# AK9750_Human_Movement_Sensor_Breakout.net
KiCad netlist of a schematic drawn in EAGLE
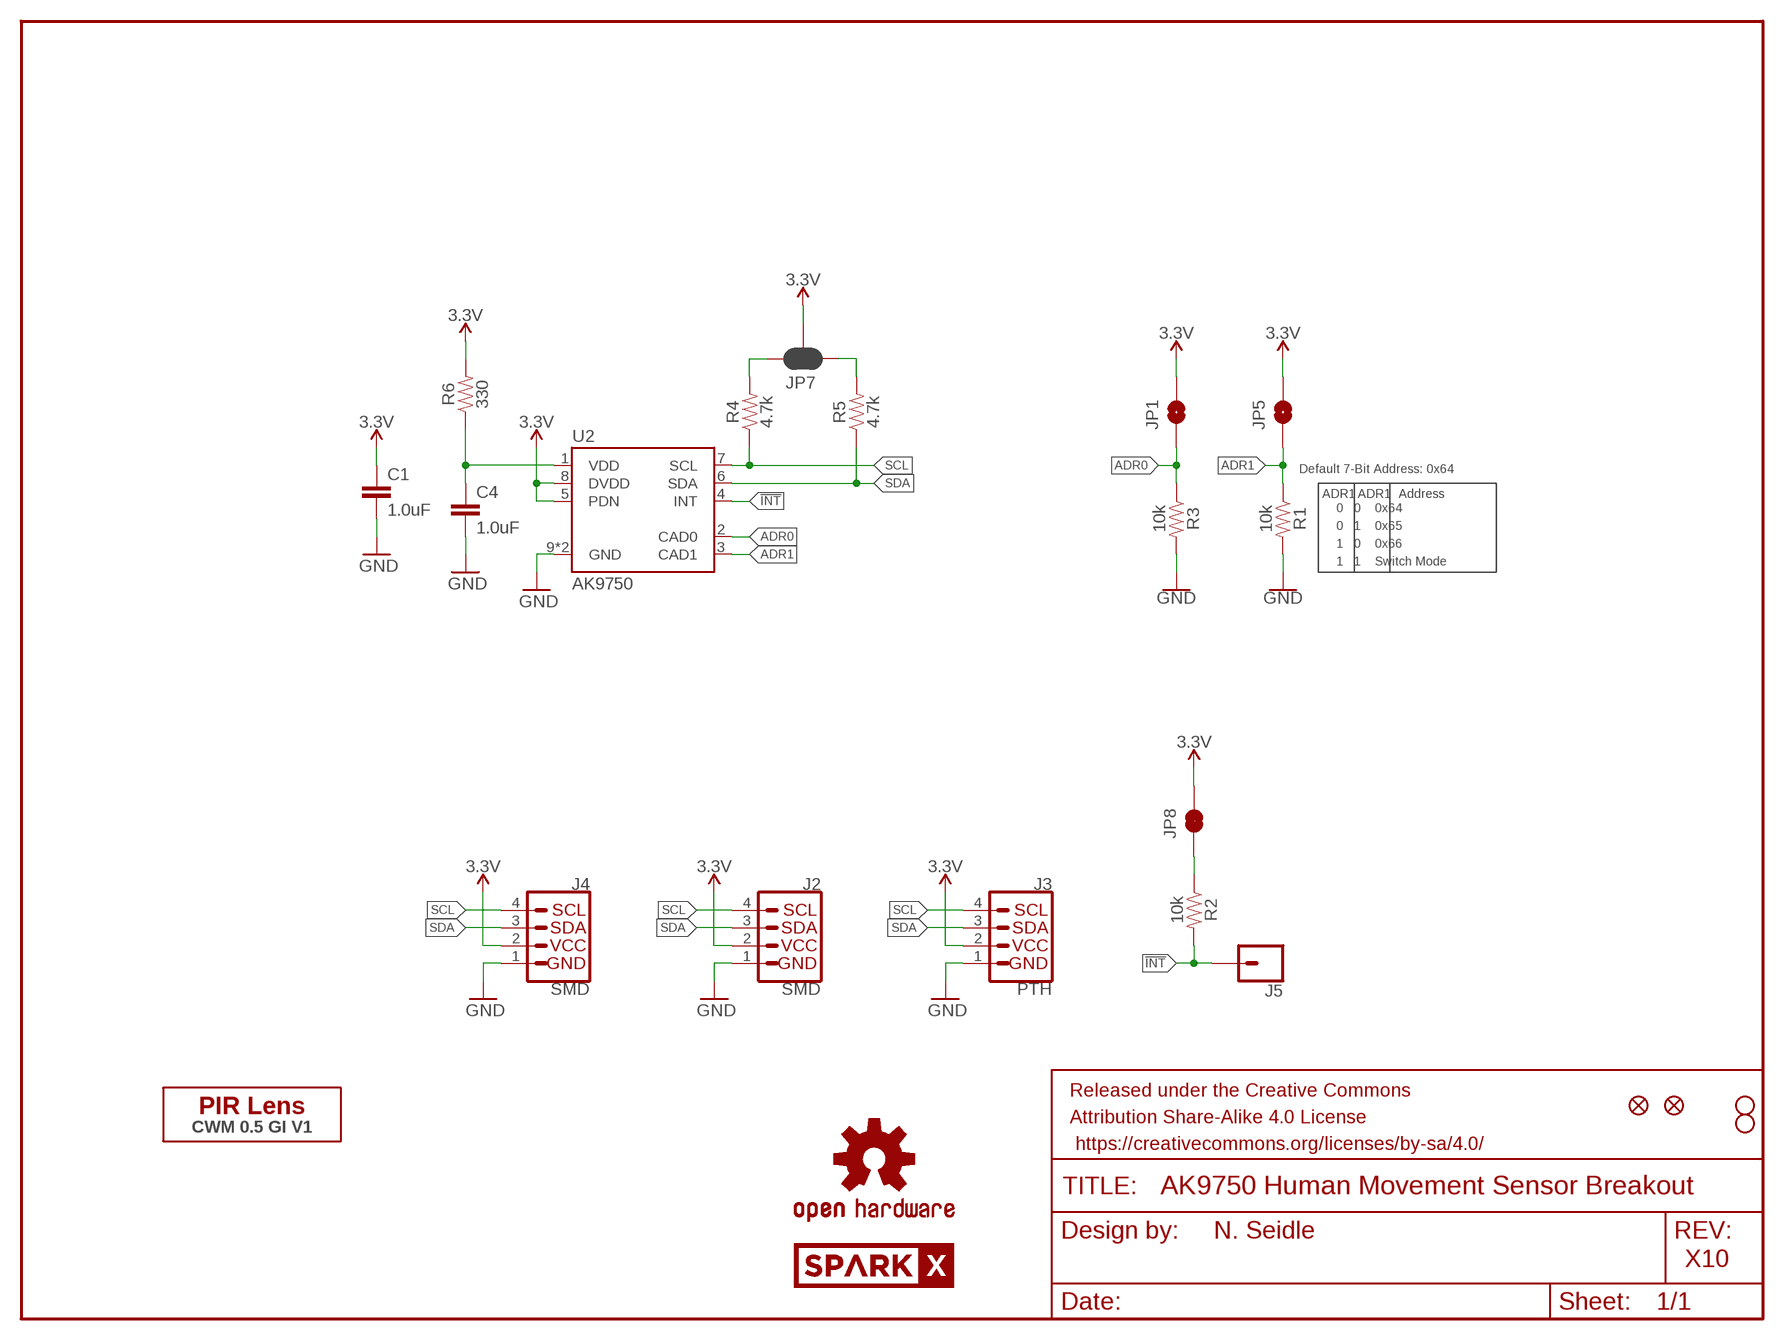
[diagram p0: schematic, sheet 1]

(export (version "E")
  (design (tool "Eeschema 10.0.6"))
  (components
    (comp (ref "C1")
      (value "1.0uF")
      (footprint "eagle-import:0603")
      (libsource (lib "eagle-import") (part "1.0UF-0603-16V-10%"))
    )
    (comp (ref "C4")
      (value "1.0uF")
      (footprint "eagle-import:0603")
      (libsource (lib "eagle-import") (part "1.0UF-0603-16V-10%"))
    )
    (comp (ref "FRAME1")
      (value "FRAME-LETTER")
      (footprint "eagle-import:CREATIVE_COMMONS")
      (libsource (lib "eagle-import") (part "FRAME-LETTER"))
    )
    (comp (ref "J2")
      (value "SMD")
      (footprint "eagle-import:1X04_1MM_RA")
      (libsource (lib "eagle-import") (part "I2C_STANDARDJS-1MM"))
    )
    (comp (ref "J3")
      (value "PTH")
      (footprint "eagle-import:1X04_NO_SILK")
      (libsource (lib "eagle-import") (part "I2C_STANDARD_NO_SILK"))
    )
    (comp (ref "J4")
      (value "SMD")
      (footprint "eagle-import:1X04_1MM_RA")
      (libsource (lib "eagle-import") (part "I2C_STANDARDJS-1MM"))
    )
    (comp (ref "J5")
      (value "CONN_01PTH_NO_SILK_YES_STOP")
      (footprint "eagle-import:1X01_NO_SILK")
      (libsource (lib "eagle-import") (part "CONN_01PTH_NO_SILK_YES_STOP"))
    )
    (comp (ref "JP1")
      (value "JUMPER-SMT_2_NO_SILK")
      (footprint "eagle-import:SMT-JUMPER_2_NO_SILK")
      (libsource (lib "eagle-import") (part "JUMPER-SMT_2_NO_SILK"))
    )
    (comp (ref "JP2")
      (value "FIDUCIALUFIDUCIAL")
      (footprint "eagle-import:MICRO-FIDUCIAL")
      (libsource (lib "eagle-import") (part "FIDUCIALUFIDUCIAL"))
    )
    (comp (ref "JP3")
      (value "STAND-OFF")
      (footprint "eagle-import:STAND-OFF")
      (libsource (lib "eagle-import") (part "STAND-OFF"))
    )
    (comp (ref "JP4")
      (value "STAND-OFF")
      (footprint "eagle-import:STAND-OFF")
      (libsource (lib "eagle-import") (part "STAND-OFF"))
    )
    (comp (ref "JP5")
      (value "JUMPER-SMT_2_NO_SILK")
      (footprint "eagle-import:SMT-JUMPER_2_NO_SILK")
      (libsource (lib "eagle-import") (part "JUMPER-SMT_2_NO_SILK"))
    )
    (comp (ref "JP6")
      (value "FIDUCIALUFIDUCIAL")
      (footprint "eagle-import:MICRO-FIDUCIAL")
      (libsource (lib "eagle-import") (part "FIDUCIALUFIDUCIAL"))
    )
    (comp (ref "JP7")
      (value "JUMPER-SMT_3_2-NC_PASTE_SILK")
      (footprint "eagle-import:SMT-JUMPER_3_2-NC_PASTE_SILK")
      (libsource (lib "eagle-import") (part "JUMPER-SMT_3_2-NC_PASTE_SILK"))
    )
    (comp (ref "JP8")
      (value "JUMPER-SMT_2_NC_TRACE_SILK")
      (footprint "eagle-import:SMT-JUMPER_2_NC_TRACE_SILK")
      (libsource (lib "eagle-import") (part "JUMPER-SMT_2_NC_TRACE_SILK"))
    )
    (comp (ref "LOGO1")
      (value "OSHW-LOGOMINI")
      (footprint "eagle-import:OSHW-LOGO-MINI")
      (libsource (lib "eagle-import") (part "OSHW-LOGOMINI"))
    )
    (comp (ref "R1")
      (value "10k")
      (footprint "eagle-import:0603")
      (libsource (lib "eagle-import") (part "10KOHM-0603-1/10W-1%"))
    )
    (comp (ref "R2")
      (value "10k")
      (footprint "eagle-import:0603")
      (libsource (lib "eagle-import") (part "10KOHM-0603-1/10W-1%"))
    )
    (comp (ref "R3")
      (value "10k")
      (footprint "eagle-import:0603")
      (libsource (lib "eagle-import") (part "10KOHM-0603-1/10W-1%"))
    )
    (comp (ref "R4")
      (value "4.7k")
      (footprint "eagle-import:0603")
      (libsource (lib "eagle-import") (part "4.7KOHM-0603-1/10W-1%"))
    )
    (comp (ref "R5")
      (value "4.7k")
      (footprint "eagle-import:0603")
      (libsource (lib "eagle-import") (part "4.7KOHM-0603-1/10W-1%"))
    )
    (comp (ref "R6")
      (value "330")
      (footprint "eagle-import:0603")
      (libsource (lib "eagle-import") (part "330OHM-0603-1/10W-1%"))
    )
    (comp (ref "U$1")
      (value "SPARKX-LOGO4")
      (footprint "eagle-import:SPARKX-MEDIUM")
      (libsource (lib "eagle-import") (part "SPARKX-LOGO4"))
    )
    (comp (ref "U$2")
      (value "SPARKX-LOGO4")
      (footprint "eagle-import:SPARKX-MEDIUM")
      (libsource (lib "eagle-import") (part "SPARKX-LOGO4"))
    )
    (comp (ref "U$3")
      (value "CWM 0.5 GI V1")
      (footprint "eagle-import:LENS-CWM-0.5-GI-V1")
      (libsource (lib "eagle-import") (part "PIR-LENSCWM-0.5-GI-V1"))
    )
    (comp (ref "U2")
      (value "AK9750")
      (footprint "eagle-import:SON10")
      (libsource (lib "eagle-import") (part "AK9750"))
    )
  )
  (nets
    (net (code "1") (name "/~{INT}") (class "Default")
      (node (ref "J5") (pin "1") (pinfunction "1_1") (pintype "passive"))
      (node (ref "R2") (pin "2") (pinfunction "2_2") (pintype "passive"))
      (node (ref "U2") (pin "4") (pinfunction "INT_4") (pintype "bidirectional"))
    )
    (net (code "2") (name "3.3V") (class "Default")
      (node (ref "C1") (pin "1") (pinfunction "1_1") (pintype "passive"))
      (node (ref "J2") (pin "2") (pinfunction "VCC_2") (pintype "power_in"))
      (node (ref "J3") (pin "2") (pinfunction "VCC_2") (pintype "power_in"))
      (node (ref "J4") (pin "2") (pinfunction "VCC_2") (pintype "power_in"))
      (node (ref "JP1") (pin "2") (pinfunction "2_2") (pintype "passive"))
      (node (ref "JP5") (pin "2") (pinfunction "2_2") (pintype "passive"))
      (node (ref "JP7") (pin "2") (pinfunction "2_2") (pintype "passive"))
      (node (ref "JP8") (pin "2") (pinfunction "2_2") (pintype "passive"))
      (node (ref "R6") (pin "2") (pinfunction "2_2") (pintype "passive"))
      (node (ref "U2") (pin "5") (pinfunction "PDN_5") (pintype "bidirectional"))
      (node (ref "U2") (pin "8") (pinfunction "DVDD_8") (pintype "bidirectional"))
    )
    (net (code "3") (name "ADR0") (class "Default")
      (node (ref "JP1") (pin "1") (pinfunction "1_1") (pintype "passive"))
      (node (ref "R3") (pin "1") (pinfunction "1_1") (pintype "passive"))
      (node (ref "U2") (pin "2") (pinfunction "CAD0_2") (pintype "bidirectional"))
    )
    (net (code "4") (name "ADR1") (class "Default")
      (node (ref "JP5") (pin "1") (pinfunction "1_1") (pintype "passive"))
      (node (ref "R1") (pin "1") (pinfunction "1_1") (pintype "passive"))
      (node (ref "U2") (pin "3") (pinfunction "CAD1_3") (pintype "bidirectional"))
    )
    (net (code "5") (name "GND") (class "Default")
      (node (ref "C1") (pin "2") (pinfunction "2_2") (pintype "passive"))
      (node (ref "C4") (pin "2") (pinfunction "2_2") (pintype "passive"))
      (node (ref "J2") (pin "1") (pinfunction "GND_1") (pintype "power_in"))
      (node (ref "J3") (pin "1") (pinfunction "GND_1") (pintype "power_in"))
      (node (ref "J4") (pin "1") (pinfunction "GND_1") (pintype "power_in"))
      (node (ref "R1") (pin "2") (pinfunction "2_2") (pintype "passive"))
      (node (ref "R3") (pin "2") (pinfunction "2_2") (pintype "passive"))
      (node (ref "U2") (pin "10") (pinfunction "GND_10") (pintype "bidirectional"))
      (node (ref "U2") (pin "9") (pinfunction "GND_9") (pintype "bidirectional"))
    )
    (net (code "6") (name "Net-(JP7-Pad1)") (class "Default")
      (node (ref "JP7") (pin "1") (pinfunction "1_1") (pintype "passive"))
      (node (ref "R5") (pin "2") (pinfunction "2_2") (pintype "passive"))
    )
    (net (code "7") (name "Net-(JP7-Pad3)") (class "Default")
      (node (ref "JP7") (pin "3") (pinfunction "3_3") (pintype "passive"))
      (node (ref "R4") (pin "2") (pinfunction "2_2") (pintype "passive"))
    )
    (net (code "8") (name "Net-(JP8-Pad1)") (class "Default")
      (node (ref "JP8") (pin "1") (pinfunction "1_1") (pintype "passive"))
      (node (ref "R2") (pin "1") (pinfunction "1_1") (pintype "passive"))
    )
    (net (code "9") (name "Net-(U2-VDD)") (class "Default")
      (node (ref "C4") (pin "1") (pinfunction "1_1") (pintype "passive"))
      (node (ref "R6") (pin "1") (pinfunction "1_1") (pintype "passive"))
      (node (ref "U2") (pin "1") (pinfunction "VDD_1") (pintype "bidirectional"))
    )
    (net (code "10") (name "SCL") (class "Default")
      (node (ref "J2") (pin "4") (pinfunction "SCL_4") (pintype "passive"))
      (node (ref "J3") (pin "4") (pinfunction "SCL_4") (pintype "passive"))
      (node (ref "J4") (pin "4") (pinfunction "SCL_4") (pintype "passive"))
      (node (ref "R4") (pin "1") (pinfunction "1_1") (pintype "passive"))
      (node (ref "U2") (pin "7") (pinfunction "SCL_7") (pintype "bidirectional"))
    )
    (net (code "11") (name "SDA") (class "Default")
      (node (ref "J2") (pin "3") (pinfunction "SDA_3") (pintype "passive"))
      (node (ref "J3") (pin "3") (pinfunction "SDA_3") (pintype "passive"))
      (node (ref "J4") (pin "3") (pinfunction "SDA_3") (pintype "passive"))
      (node (ref "R5") (pin "1") (pinfunction "1_1") (pintype "passive"))
      (node (ref "U2") (pin "6") (pinfunction "SDA_6") (pintype "bidirectional"))
    )
  )
)
